# 6packRev2A.net
KiCad netlist of a schematic drawn in EAGLE
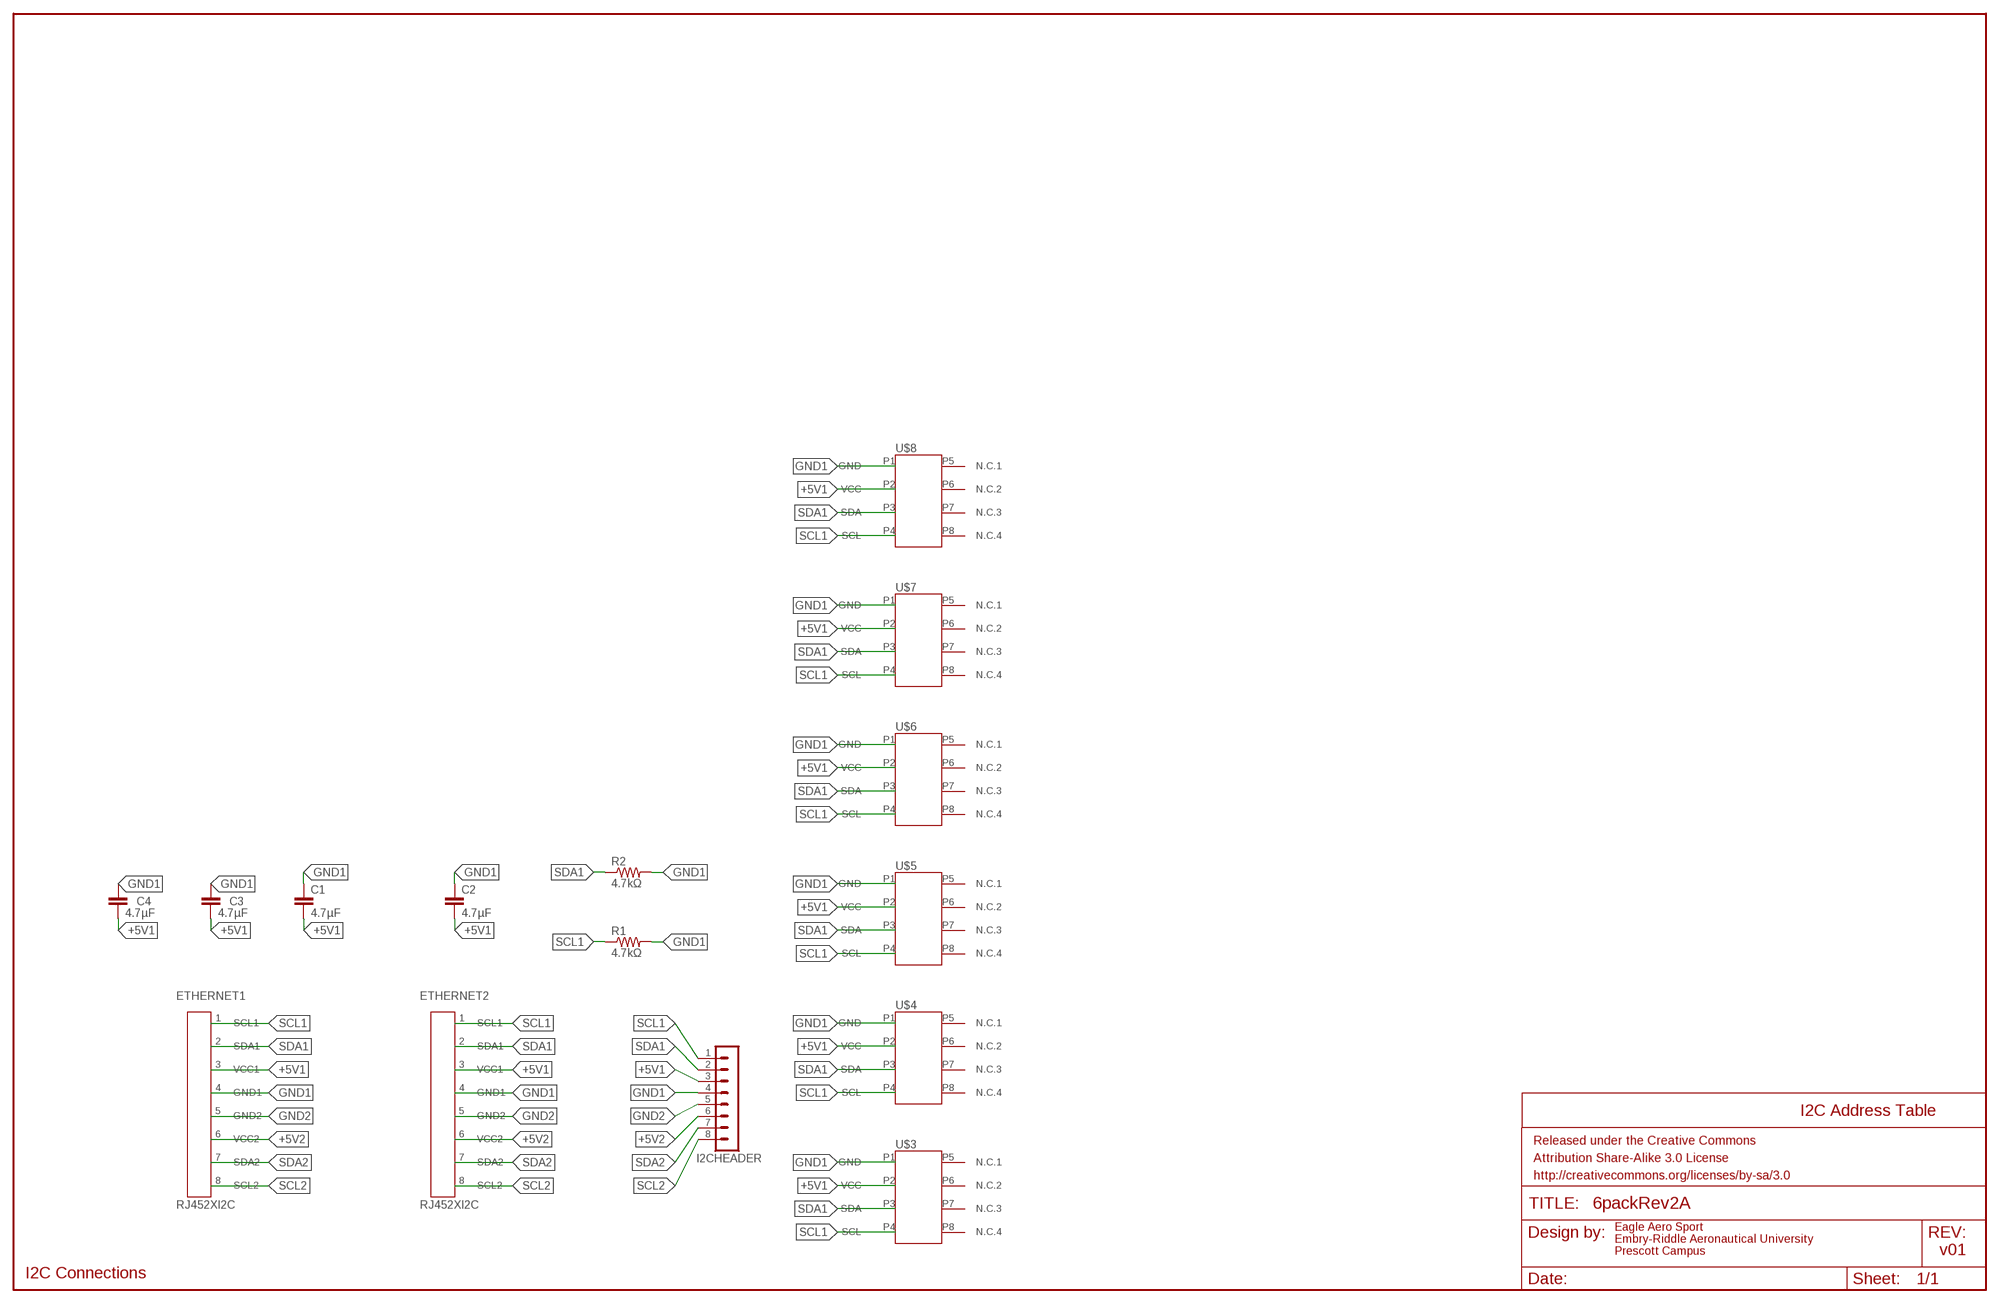
[diagram p0: schematic, sheet 1]

(export (version "E")
  (design (tool "Eeschema 10.0.6"))
  (components
    (comp (ref "C1")
      (value "4.7µF")
      (footprint "eagle-import:0805")
      (libsource (lib "eagle-import") (part "0.33UF/330NF-0805-50V-10%"))
    )
    (comp (ref "C2")
      (value "4.7µF")
      (footprint "eagle-import:0805")
      (libsource (lib "eagle-import") (part "0.33UF/330NF-0805-50V-10%"))
    )
    (comp (ref "C3")
      (value "4.7µF")
      (footprint "eagle-import:CAP-PTH-10MM")
      (libsource (lib "eagle-import") (part "10NF-PTH-10MM-10000V-1-%"))
    )
    (comp (ref "C4")
      (value "4.7µF")
      (footprint "eagle-import:CAP-PTH-10MM")
      (libsource (lib "eagle-import") (part "10NF-PTH-10MM-10000V-1-%"))
    )
    (comp (ref "ETHERNET1")
      (value "RJ452XI2C")
      (footprint "eagle-import:RJ45-8")
      (libsource (lib "eagle-import") (part "RJ452XI2C"))
    )
    (comp (ref "ETHERNET2")
      (value "RJ452XI2C")
      (footprint "eagle-import:RJ45-8")
      (libsource (lib "eagle-import") (part "RJ452XI2C"))
    )
    (comp (ref "FRAME1")
      (value "FRAME-LEDGER")
      (footprint "eagle-import:CREATIVE_COMMONS")
      (libsource (lib "eagle-import") (part "FRAME-LEDGER"))
    )
    (comp (ref "I2CHEADER")
      (value "MA08-1")
      (footprint "eagle-import:MA08-1")
      (libsource (lib "eagle-import") (part "MA08-1"))
    )
    (comp (ref "R1")
      (value "4.7kΩ")
      (footprint "eagle-import:0207_10")
      (libsource (lib "eagle-import") (part "R-US_0207/10"))
    )
    (comp (ref "R2")
      (value "4.7kΩ")
      (footprint "eagle-import:0207_10")
      (libsource (lib "eagle-import") (part "R-US_0207/10"))
    )
    (comp (ref "U$3")
      (value "AMS5915")
      (footprint "eagle-import:DIP8W")
      (libsource (lib "eagle-import") (part "AMS5915"))
    )
    (comp (ref "U$4")
      (value "AMS5915")
      (footprint "eagle-import:DIP8W")
      (libsource (lib "eagle-import") (part "AMS5915"))
    )
    (comp (ref "U$5")
      (value "AMS5915")
      (footprint "eagle-import:DIP8W")
      (libsource (lib "eagle-import") (part "AMS5915"))
    )
    (comp (ref "U$6")
      (value "AMS5915")
      (footprint "eagle-import:DIP8W")
      (libsource (lib "eagle-import") (part "AMS5915"))
    )
    (comp (ref "U$7")
      (value "AMS5915")
      (footprint "eagle-import:DIP8W")
      (libsource (lib "eagle-import") (part "AMS5915"))
    )
    (comp (ref "U$8")
      (value "AMS5915")
      (footprint "eagle-import:DIP8W")
      (libsource (lib "eagle-import") (part "AMS5915"))
    )
  )
  (nets
    (net (code "1") (name "+5V1") (class "Default")
      (node (ref "C1") (pin "2") (pinfunction "2_2") (pintype "passive"))
      (node (ref "C2") (pin "2") (pinfunction "2_2") (pintype "passive"))
      (node (ref "C3") (pin "2") (pinfunction "2_2") (pintype "passive"))
      (node (ref "C4") (pin "2") (pinfunction "2_2") (pintype "passive"))
      (node (ref "ETHERNET1") (pin "3") (pinfunction "VCC1_3") (pintype "bidirectional"))
      (node (ref "ETHERNET2") (pin "3") (pinfunction "VCC1_3") (pintype "bidirectional"))
      (node (ref "I2CHEADER") (pin "3") (pinfunction "3_3") (pintype "passive"))
      (node (ref "U$3") (pin "P2") (pinfunction "VCC_P2") (pintype "power_in"))
      (node (ref "U$4") (pin "P2") (pinfunction "VCC_P2") (pintype "power_in"))
      (node (ref "U$5") (pin "P2") (pinfunction "VCC_P2") (pintype "power_in"))
      (node (ref "U$6") (pin "P2") (pinfunction "VCC_P2") (pintype "power_in"))
      (node (ref "U$7") (pin "P2") (pinfunction "VCC_P2") (pintype "power_in"))
      (node (ref "U$8") (pin "P2") (pinfunction "VCC_P2") (pintype "power_in"))
    )
    (net (code "2") (name "+5V2") (class "Default")
      (node (ref "ETHERNET1") (pin "6") (pinfunction "VCC2_6") (pintype "bidirectional"))
      (node (ref "ETHERNET2") (pin "6") (pinfunction "VCC2_6") (pintype "bidirectional"))
      (node (ref "I2CHEADER") (pin "6") (pinfunction "6_6") (pintype "passive"))
    )
    (net (code "3") (name "GND1") (class "Default")
      (node (ref "C1") (pin "1") (pinfunction "1_1") (pintype "passive"))
      (node (ref "C2") (pin "1") (pinfunction "1_1") (pintype "passive"))
      (node (ref "C3") (pin "1") (pinfunction "1_1") (pintype "passive"))
      (node (ref "C4") (pin "1") (pinfunction "1_1") (pintype "passive"))
      (node (ref "ETHERNET1") (pin "4") (pinfunction "GND1_4") (pintype "bidirectional"))
      (node (ref "ETHERNET2") (pin "4") (pinfunction "GND1_4") (pintype "bidirectional"))
      (node (ref "I2CHEADER") (pin "4") (pinfunction "4_4") (pintype "passive"))
      (node (ref "R1") (pin "2") (pinfunction "2_2") (pintype "passive"))
      (node (ref "R2") (pin "2") (pinfunction "2_2") (pintype "passive"))
      (node (ref "U$3") (pin "P1") (pinfunction "GND_P1") (pintype "bidirectional"))
      (node (ref "U$4") (pin "P1") (pinfunction "GND_P1") (pintype "bidirectional"))
      (node (ref "U$5") (pin "P1") (pinfunction "GND_P1") (pintype "bidirectional"))
      (node (ref "U$6") (pin "P1") (pinfunction "GND_P1") (pintype "bidirectional"))
      (node (ref "U$7") (pin "P1") (pinfunction "GND_P1") (pintype "bidirectional"))
      (node (ref "U$8") (pin "P1") (pinfunction "GND_P1") (pintype "bidirectional"))
    )
    (net (code "4") (name "GND2") (class "Default")
      (node (ref "ETHERNET1") (pin "5") (pinfunction "GND2_5") (pintype "bidirectional"))
      (node (ref "ETHERNET2") (pin "5") (pinfunction "GND2_5") (pintype "bidirectional"))
      (node (ref "I2CHEADER") (pin "5") (pinfunction "5_5") (pintype "passive"))
    )
    (net (code "5") (name "SCL1") (class "Default")
      (node (ref "ETHERNET1") (pin "1") (pinfunction "SCL1_1") (pintype "bidirectional"))
      (node (ref "ETHERNET2") (pin "1") (pinfunction "SCL1_1") (pintype "bidirectional"))
      (node (ref "I2CHEADER") (pin "1") (pinfunction "1_1") (pintype "passive"))
      (node (ref "R1") (pin "1") (pinfunction "1_1") (pintype "passive"))
      (node (ref "U$3") (pin "P4") (pinfunction "SCL_P4") (pintype "bidirectional"))
      (node (ref "U$4") (pin "P4") (pinfunction "SCL_P4") (pintype "bidirectional"))
      (node (ref "U$5") (pin "P4") (pinfunction "SCL_P4") (pintype "bidirectional"))
      (node (ref "U$6") (pin "P4") (pinfunction "SCL_P4") (pintype "bidirectional"))
      (node (ref "U$7") (pin "P4") (pinfunction "SCL_P4") (pintype "bidirectional"))
      (node (ref "U$8") (pin "P4") (pinfunction "SCL_P4") (pintype "bidirectional"))
    )
    (net (code "6") (name "SCL2") (class "Default")
      (node (ref "ETHERNET1") (pin "8") (pinfunction "SCL2_8") (pintype "bidirectional"))
      (node (ref "ETHERNET2") (pin "8") (pinfunction "SCL2_8") (pintype "bidirectional"))
      (node (ref "I2CHEADER") (pin "8") (pinfunction "8_8") (pintype "passive"))
    )
    (net (code "7") (name "SDA1") (class "Default")
      (node (ref "ETHERNET1") (pin "2") (pinfunction "SDA1_2") (pintype "bidirectional"))
      (node (ref "ETHERNET2") (pin "2") (pinfunction "SDA1_2") (pintype "bidirectional"))
      (node (ref "I2CHEADER") (pin "2") (pinfunction "2_2") (pintype "passive"))
      (node (ref "R2") (pin "1") (pinfunction "1_1") (pintype "passive"))
      (node (ref "U$3") (pin "P3") (pinfunction "SDA_P3") (pintype "bidirectional"))
      (node (ref "U$4") (pin "P3") (pinfunction "SDA_P3") (pintype "bidirectional"))
      (node (ref "U$5") (pin "P3") (pinfunction "SDA_P3") (pintype "bidirectional"))
      (node (ref "U$6") (pin "P3") (pinfunction "SDA_P3") (pintype "bidirectional"))
      (node (ref "U$7") (pin "P3") (pinfunction "SDA_P3") (pintype "bidirectional"))
      (node (ref "U$8") (pin "P3") (pinfunction "SDA_P3") (pintype "bidirectional"))
    )
    (net (code "8") (name "SDA2") (class "Default")
      (node (ref "ETHERNET1") (pin "7") (pinfunction "SDA2_7") (pintype "bidirectional"))
      (node (ref "ETHERNET2") (pin "7") (pinfunction "SDA2_7") (pintype "bidirectional"))
      (node (ref "I2CHEADER") (pin "7") (pinfunction "7_7") (pintype "passive"))
    )
    (net (code "9") (name "unconnected-(U$3-N.C.1-PadP5)") (class "Default")
      (node (ref "U$3") (pin "P5") (pinfunction "N.C.1_P5") (pintype "no_connect"))
    )
    (net (code "10") (name "unconnected-(U$3-N.C.2-PadP6)") (class "Default")
      (node (ref "U$3") (pin "P6") (pinfunction "N.C.2_P6") (pintype "no_connect"))
    )
    (net (code "11") (name "unconnected-(U$3-N.C.3-PadP7)") (class "Default")
      (node (ref "U$3") (pin "P7") (pinfunction "N.C.3_P7") (pintype "no_connect"))
    )
    (net (code "12") (name "unconnected-(U$3-N.C.4-PadP8)") (class "Default")
      (node (ref "U$3") (pin "P8") (pinfunction "N.C.4_P8") (pintype "no_connect"))
    )
    (net (code "13") (name "unconnected-(U$4-N.C.1-PadP5)") (class "Default")
      (node (ref "U$4") (pin "P5") (pinfunction "N.C.1_P5") (pintype "no_connect"))
    )
    (net (code "14") (name "unconnected-(U$4-N.C.2-PadP6)") (class "Default")
      (node (ref "U$4") (pin "P6") (pinfunction "N.C.2_P6") (pintype "no_connect"))
    )
    (net (code "15") (name "unconnected-(U$4-N.C.3-PadP7)") (class "Default")
      (node (ref "U$4") (pin "P7") (pinfunction "N.C.3_P7") (pintype "no_connect"))
    )
    (net (code "16") (name "unconnected-(U$4-N.C.4-PadP8)") (class "Default")
      (node (ref "U$4") (pin "P8") (pinfunction "N.C.4_P8") (pintype "no_connect"))
    )
    (net (code "17") (name "unconnected-(U$5-N.C.1-PadP5)") (class "Default")
      (node (ref "U$5") (pin "P5") (pinfunction "N.C.1_P5") (pintype "no_connect"))
    )
    (net (code "18") (name "unconnected-(U$5-N.C.2-PadP6)") (class "Default")
      (node (ref "U$5") (pin "P6") (pinfunction "N.C.2_P6") (pintype "no_connect"))
    )
    (net (code "19") (name "unconnected-(U$5-N.C.3-PadP7)") (class "Default")
      (node (ref "U$5") (pin "P7") (pinfunction "N.C.3_P7") (pintype "no_connect"))
    )
    (net (code "20") (name "unconnected-(U$5-N.C.4-PadP8)") (class "Default")
      (node (ref "U$5") (pin "P8") (pinfunction "N.C.4_P8") (pintype "no_connect"))
    )
    (net (code "21") (name "unconnected-(U$6-N.C.1-PadP5)") (class "Default")
      (node (ref "U$6") (pin "P5") (pinfunction "N.C.1_P5") (pintype "no_connect"))
    )
    (net (code "22") (name "unconnected-(U$6-N.C.2-PadP6)") (class "Default")
      (node (ref "U$6") (pin "P6") (pinfunction "N.C.2_P6") (pintype "no_connect"))
    )
    (net (code "23") (name "unconnected-(U$6-N.C.3-PadP7)") (class "Default")
      (node (ref "U$6") (pin "P7") (pinfunction "N.C.3_P7") (pintype "no_connect"))
    )
    (net (code "24") (name "unconnected-(U$6-N.C.4-PadP8)") (class "Default")
      (node (ref "U$6") (pin "P8") (pinfunction "N.C.4_P8") (pintype "no_connect"))
    )
    (net (code "25") (name "unconnected-(U$7-N.C.1-PadP5)") (class "Default")
      (node (ref "U$7") (pin "P5") (pinfunction "N.C.1_P5") (pintype "no_connect"))
    )
    (net (code "26") (name "unconnected-(U$7-N.C.2-PadP6)") (class "Default")
      (node (ref "U$7") (pin "P6") (pinfunction "N.C.2_P6") (pintype "no_connect"))
    )
    (net (code "27") (name "unconnected-(U$7-N.C.3-PadP7)") (class "Default")
      (node (ref "U$7") (pin "P7") (pinfunction "N.C.3_P7") (pintype "no_connect"))
    )
    (net (code "28") (name "unconnected-(U$7-N.C.4-PadP8)") (class "Default")
      (node (ref "U$7") (pin "P8") (pinfunction "N.C.4_P8") (pintype "no_connect"))
    )
    (net (code "29") (name "unconnected-(U$8-N.C.1-PadP5)") (class "Default")
      (node (ref "U$8") (pin "P5") (pinfunction "N.C.1_P5") (pintype "no_connect"))
    )
    (net (code "30") (name "unconnected-(U$8-N.C.2-PadP6)") (class "Default")
      (node (ref "U$8") (pin "P6") (pinfunction "N.C.2_P6") (pintype "no_connect"))
    )
    (net (code "31") (name "unconnected-(U$8-N.C.3-PadP7)") (class "Default")
      (node (ref "U$8") (pin "P7") (pinfunction "N.C.3_P7") (pintype "no_connect"))
    )
    (net (code "32") (name "unconnected-(U$8-N.C.4-PadP8)") (class "Default")
      (node (ref "U$8") (pin "P8") (pinfunction "N.C.4_P8") (pintype "no_connect"))
    )
  )
)
